# APC1_Wireless.net
KiCad netlist of a schematic drawn in Altium Designer
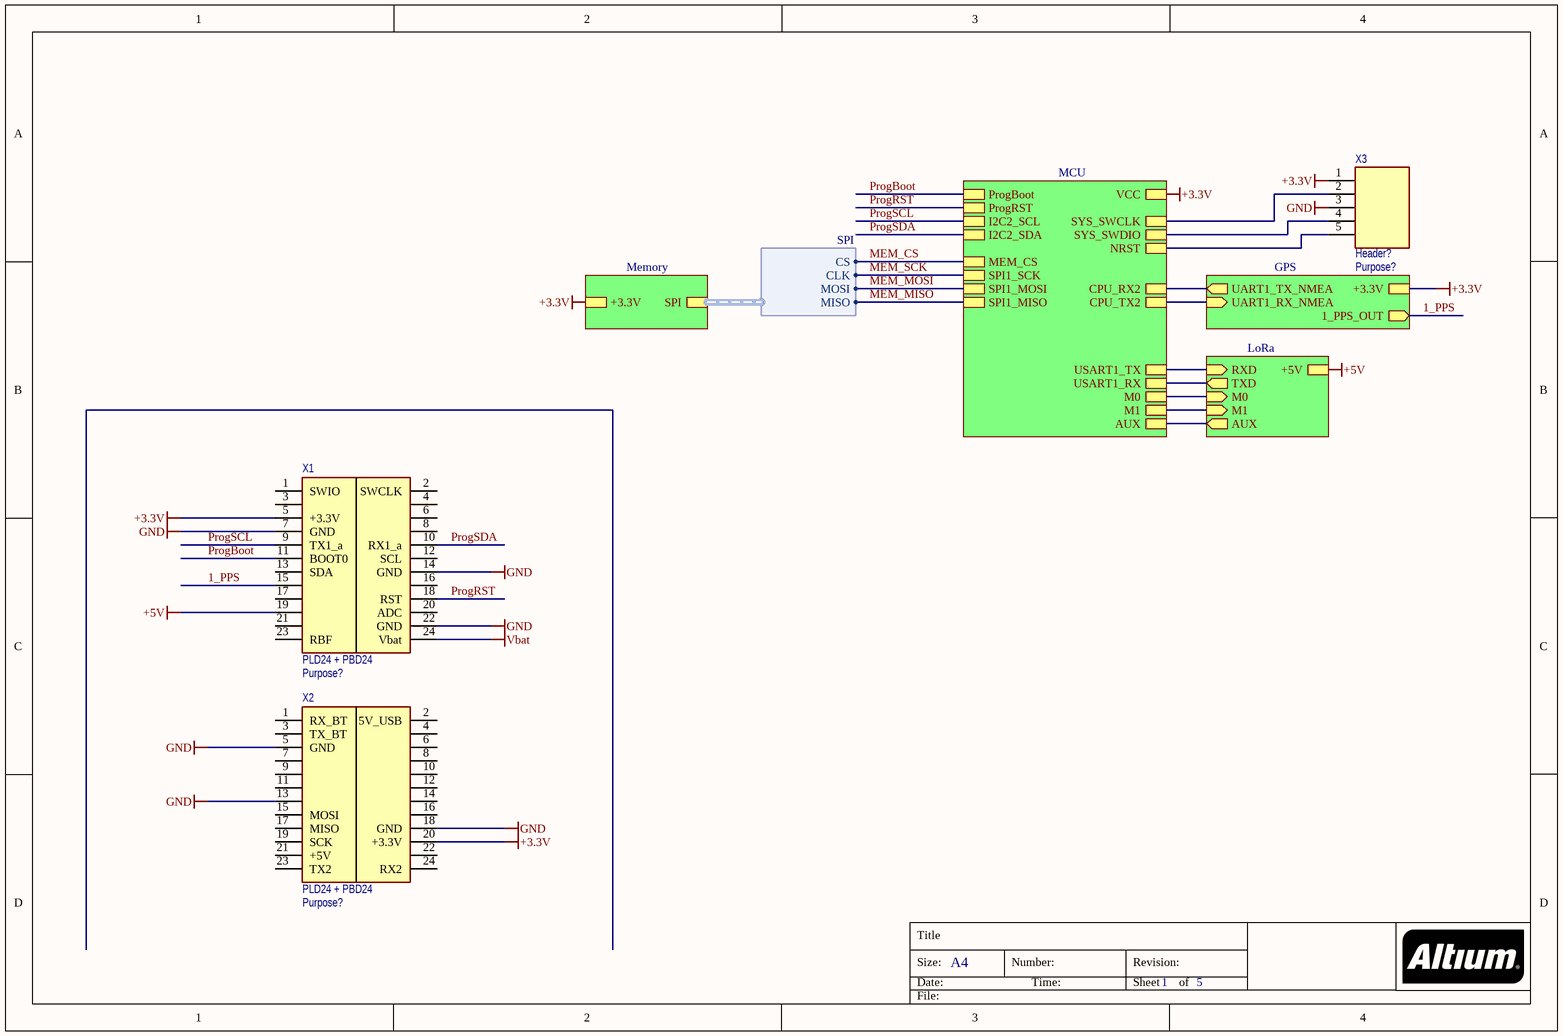
[diagram p0: APC1_Wireless.SchDoc]

(export (version "E")
  (design (tool "Eeschema 10.0.6"))
  (components
    (comp (ref "X1")
      (value "PLD24 + PBD24")
      (footprint "PICOSAT_CNN")
      (description "10x2 header")
      (fields (field (name "PURPOSE") "Purpose?"))
      (libsource (lib "connectors") (part "Header 2x12"))
    )
    (comp (ref "X2")
      (value "PLD24 + PBD24")
      (footprint "PICOSAT_CNN")
      (description "10x2 header")
      (fields (field (name "PURPOSE") "Purpose?"))
      (libsource (lib "connectors") (part "Header 2x12"))
    )
    (comp (ref "X3")
      (value "Header?")
      (footprint "PLS-5R-2.54")
      (description "5x1 header")
      (fields (field (name "PURPOSE") "Purpose?"))
      (libsource (lib "connectors") (part "Header 1x5"))
    )
  )
  (nets
    (net (code "2") (name "+3.3V") (class "Default")
      (node (ref "X1") (pin "5") (pinfunction "GND_5") (pintype "passive"))
      (node (ref "X2") (pin "20") (pinfunction "+3.3V_20") (pintype "passive"))
      (node (ref "X3") (pin "1") (pinfunction "10_1") (pintype "passive"))
    )
    (net (code "3") (name "+5V") (class "Default")
      (node (ref "X1") (pin "19") (pinfunction "SCK_19") (pintype "passive"))
    )
    (net (code "4") (name "/1_PPS") (class "Default")
      (node (ref "X1") (pin "15") (pinfunction "MOSI_15") (pintype "passive"))
    )
    (net (code "13") (name "/NRST") (class "Default")
      (node (ref "X3") (pin "5") (pinfunction "14_5") (pintype "passive"))
    )
    (net (code "14") (name "/ProgBoot") (class "Default") (node (ref "X1") (pin "11") (pintype "passive")))
    (net (code "15") (name "/ProgRST") (class "Default")
      (node (ref "X1") (pin "18") (pinfunction "GND_18") (pintype "passive"))
    )
    (net (code "16") (name "/ProgSCL") (class "Default") (node (ref "X1") (pin "9") (pintype "passive")))
    (net (code "17") (name "/ProgSDA") (class "Default") (node (ref "X1") (pin "10") (pintype "passive")))
    (net (code "19") (name "/SYS_SWCLK") (class "Default")
      (node (ref "X3") (pin "2") (pinfunction "11_2") (pintype "passive"))
    )
    (net (code "20") (name "/SYS_SWDIO") (class "Default")
      (node (ref "X3") (pin "4") (pinfunction "13_4") (pintype "passive"))
    )
    (net (code "24") (name "GND") (class "Default")
      (node (ref "X1") (pin "14") (pintype "passive"))
      (node (ref "X1") (pin "22") (pintype "passive"))
      (node (ref "X1") (pin "7") (pintype "passive"))
      (node (ref "X2") (pin "13") (pintype "passive"))
      (node (ref "X2") (pin "18") (pinfunction "GND_18") (pintype "passive"))
      (node (ref "X2") (pin "5") (pinfunction "GND_5") (pintype "passive"))
      (node (ref "X3") (pin "3") (pinfunction "12_3") (pintype "passive"))
    )
    (net (code "25") (name "Vbat") (class "Default")
      (node (ref "X1") (pin "24") (pinfunction "RX2_24") (pintype "passive"))
    )
    (net (code "26") (name "unconnected-(X1-+3.3V-Pad20)") (class "Default")
      (node (ref "X1") (pin "20") (pinfunction "+3.3V_20") (pintype "passive"))
    )
    (net (code "27") (name "unconnected-(X1-+5V-Pad21)") (class "Default")
      (node (ref "X1") (pin "21") (pinfunction "+5V_21") (pintype "passive"))
    )
    (net (code "28") (name "unconnected-(X1-5V_USB-Pad2)") (class "Default")
      (node (ref "X1") (pin "2") (pinfunction "5V_USB_2") (pintype "passive"))
    )
    (net (code "29") (name "unconnected-(X1-MISO-Pad17)") (class "Default")
      (node (ref "X1") (pin "17") (pinfunction "MISO_17") (pintype "passive"))
    )
    (net (code "30") (name "unconnected-(X1-Pad4)") (class "Default")
      (node (ref "X1") (pin "4") (pintype "passive"))
    )
    (net (code "31") (name "unconnected-(X1-Pad6)") (class "Default")
      (node (ref "X1") (pin "6") (pintype "passive"))
    )
    (net (code "32") (name "unconnected-(X1-Pad8)") (class "Default")
      (node (ref "X1") (pin "8") (pintype "passive"))
    )
    (net (code "33") (name "unconnected-(X1-Pad12)") (class "Default")
      (node (ref "X1") (pin "12") (pintype "passive"))
    )
    (net (code "34") (name "unconnected-(X1-Pad13)") (class "Default")
      (node (ref "X1") (pin "13") (pintype "passive"))
    )
    (net (code "35") (name "unconnected-(X1-Pad16)") (class "Default")
      (node (ref "X1") (pin "16") (pintype "passive"))
    )
    (net (code "36") (name "unconnected-(X1-RX_BT-Pad1)") (class "Default")
      (node (ref "X1") (pin "1") (pinfunction "RX_BT_1") (pintype "passive"))
    )
    (net (code "37") (name "unconnected-(X1-TX2-Pad23)") (class "Default")
      (node (ref "X1") (pin "23") (pinfunction "TX2_23") (pintype "passive"))
    )
    (net (code "38") (name "unconnected-(X1-TX_BT-Pad3)") (class "Default")
      (node (ref "X1") (pin "3") (pinfunction "TX_BT_3") (pintype "passive"))
    )
    (net (code "39") (name "unconnected-(X2-+5V-Pad21)") (class "Default")
      (node (ref "X2") (pin "21") (pinfunction "+5V_21") (pintype "passive"))
    )
    (net (code "40") (name "unconnected-(X2-5V_USB-Pad2)") (class "Default")
      (node (ref "X2") (pin "2") (pinfunction "5V_USB_2") (pintype "passive"))
    )
    (net (code "41") (name "unconnected-(X2-MISO-Pad17)") (class "Default")
      (node (ref "X2") (pin "17") (pinfunction "MISO_17") (pintype "passive"))
    )
    (net (code "42") (name "unconnected-(X2-MOSI-Pad15)") (class "Default")
      (node (ref "X2") (pin "15") (pinfunction "MOSI_15") (pintype "passive"))
    )
    (net (code "43") (name "unconnected-(X2-Pad4)") (class "Default")
      (node (ref "X2") (pin "4") (pintype "passive"))
    )
    (net (code "44") (name "unconnected-(X2-Pad6)") (class "Default")
      (node (ref "X2") (pin "6") (pintype "passive"))
    )
    (net (code "45") (name "unconnected-(X2-Pad7)") (class "Default")
      (node (ref "X2") (pin "7") (pintype "passive"))
    )
    (net (code "46") (name "unconnected-(X2-Pad8)") (class "Default")
      (node (ref "X2") (pin "8") (pintype "passive"))
    )
    (net (code "47") (name "unconnected-(X2-Pad9)") (class "Default")
      (node (ref "X2") (pin "9") (pintype "passive"))
    )
    (net (code "48") (name "unconnected-(X2-Pad10)") (class "Default")
      (node (ref "X2") (pin "10") (pintype "passive"))
    )
    (net (code "49") (name "unconnected-(X2-Pad11)") (class "Default")
      (node (ref "X2") (pin "11") (pintype "passive"))
    )
    (net (code "50") (name "unconnected-(X2-Pad12)") (class "Default")
      (node (ref "X2") (pin "12") (pintype "passive"))
    )
    (net (code "51") (name "unconnected-(X2-Pad14)") (class "Default")
      (node (ref "X2") (pin "14") (pintype "passive"))
    )
    (net (code "52") (name "unconnected-(X2-Pad16)") (class "Default")
      (node (ref "X2") (pin "16") (pintype "passive"))
    )
    (net (code "53") (name "unconnected-(X2-Pad22)") (class "Default")
      (node (ref "X2") (pin "22") (pintype "passive"))
    )
    (net (code "54") (name "unconnected-(X2-RX2-Pad24)") (class "Default")
      (node (ref "X2") (pin "24") (pinfunction "RX2_24") (pintype "passive"))
    )
    (net (code "55") (name "unconnected-(X2-RX_BT-Pad1)") (class "Default")
      (node (ref "X2") (pin "1") (pinfunction "RX_BT_1") (pintype "passive"))
    )
    (net (code "56") (name "unconnected-(X2-SCK-Pad19)") (class "Default")
      (node (ref "X2") (pin "19") (pinfunction "SCK_19") (pintype "passive"))
    )
    (net (code "57") (name "unconnected-(X2-TX2-Pad23)") (class "Default")
      (node (ref "X2") (pin "23") (pinfunction "TX2_23") (pintype "passive"))
    )
    (net (code "58") (name "unconnected-(X2-TX_BT-Pad3)") (class "Default")
      (node (ref "X2") (pin "3") (pinfunction "TX_BT_3") (pintype "passive"))
    )
  )
)
